# Power_3V3_Regulator.net
KiCad netlist of a schematic drawn in Altium Designer
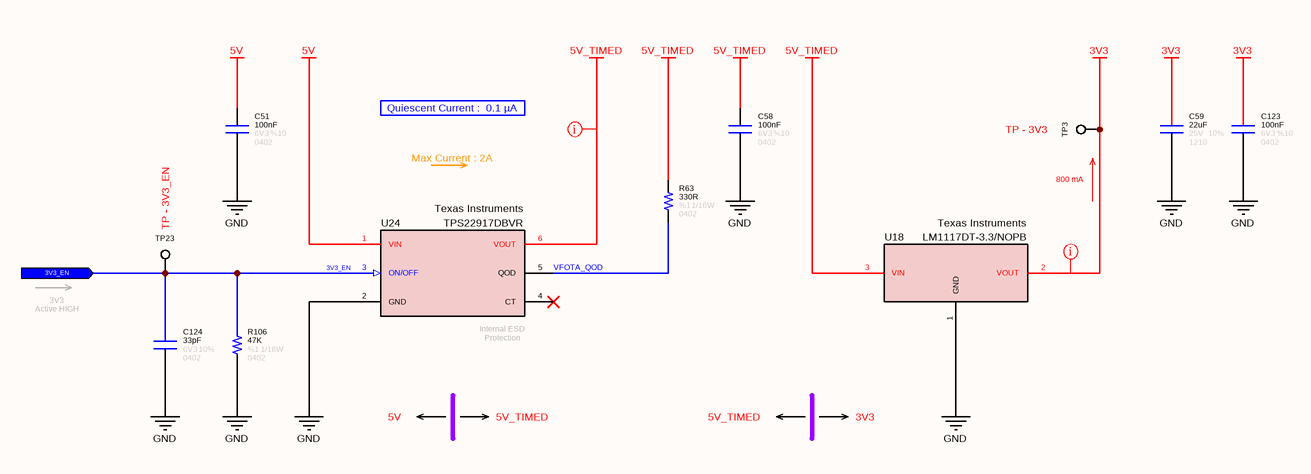
[diagram p0: Power 3V3 Regulator.SchDoc]

(export (version "E")
  (design (tool "Eeschema 10.0.6"))
  (components
    (comp (ref "C51")
      (value "100nF")
      (footprint "CAPACITOR_0402")
      (description "Capacitor - 100nF [0402-6V3] (Ceramic)")
      (fields
        (field (name "MANUFACTURER PART NUMBER") "04026D104KAT4A")
        (field (name "TOLERANCE") "%10")
        (field (name "VOLTAGE") "6V3")
        (field (name "CASE") "0402")
        (field (name "Comment") "Capacitor - 100nF [0402] (Ceramic)")
      )
      (libsource (lib "Akkoyun") (part "Capacitor - 100nF [0402-6V3]"))
    )
    (comp (ref "C58")
      (value "100nF")
      (footprint "CAPACITOR_0402")
      (description "Capacitor - 100nF [0402-6V3] (Ceramic)")
      (fields
        (field (name "MANUFACTURER PART NUMBER") "04026D104KAT4A")
        (field (name "TOLERANCE") "%10")
        (field (name "VOLTAGE") "6V3")
        (field (name "CASE") "0402")
        (field (name "Comment") "Capacitor - 100nF [0402] (Ceramic)")
      )
      (libsource (lib "Akkoyun") (part "Capacitor - 100nF [0402-6V3]"))
    )
    (comp (ref "C59")
      (value "22uF")
      (footprint "CAPACITOR_0603")
      (description "Multilayer Ceramic Capacitors MLCC - SMD/SMT 22UF 25V 10% 1210")
      (fields
        (field (name "MANUFACTURER PART NUMBER") "GRM32ER71E226KE15L")
        (field (name "TOLERANCE") "10%")
        (field (name "CASE") "1210")
        (field (name "VOLTAGE") "25V")
        (field (name "Comment") "Capacitor - 22uF [1210] (Ceramic)")
      )
      (libsource (lib "Akkoyun") (part "Capacitor - 22uF [1210-6V3]"))
    )
    (comp (ref "C123")
      (value "100nF")
      (footprint "CAPACITOR_0402")
      (description "Capacitor - 100nF [0402-6V3] (Ceramic)")
      (fields
        (field (name "MANUFACTURER PART NUMBER") "04026D104KAT4A")
        (field (name "TOLERANCE") "%10")
        (field (name "VOLTAGE") "6V3")
        (field (name "CASE") "0402")
        (field (name "Comment") "Capacitor - 100nF [0402] (Ceramic)")
      )
      (libsource (lib "Akkoyun") (part "Capacitor - 100nF [0402-6V3]"))
    )
    (comp (ref "C124")
      (value "33pF")
      (footprint "CAPACITOR_0402")
      (description "Capacitor - 33pF [0402] (Ceramic)")
      (fields
        (field (name "MANUFACTURER PART NUMBER") "C0402C330J9RACAUTO")
        (field (name "TOLERANCE") "10%")
        (field (name "CASE") "0402")
        (field (name "VOLTAGE") "6V3")
      )
      (libsource (lib "Akkoyun") (part "Capacitor - 33pF [0402-6V3]"))
    )
    (comp (ref "R63")
      (value "330R")
      (footprint "RESISTOR_0402")
      (description "Thick Film Resistors - SMD 1/16 W 330 Ohm 1%")
      (fields
        (field (name "MANUFACTURER PART NUMBER") "CRCW0402330RFKED")
        (field (name "CASE") "0402")
        (field (name "TOLERANCE") "%1")
        (field (name "POWER") "1/16W")
        (field (name "Comment") "330R - 0402 - %1 - 1/16W")
      )
      (libsource (lib "Akkoyun") (part "Resistor - 330R [0402]"))
    )
    (comp (ref "R106")
      (value "47K")
      (footprint "RESISTOR_0402")
      (description "Thick Film Resistors - SMD 1/16 W 47 KOhm 1%")
      (fields
        (field (name "MANUFACTURER PART NUMBER") "CRCW040247K0FKED")
        (field (name "TOLERANCE") "%1")
        (field (name "CASE") "0402")
        (field (name "POWER") "1/16W")
        (field (name "Comment") "47K - 0402 - %1 - 1/16W")
      )
      (libsource (lib "Akkoyun") (part "Resistor - 47K [0402]"))
    )
    (comp (ref "TP3")
      (value "TP - 3V3")
      (footprint "TP")
      (description "Test Point")
      (libsource (lib "Akkoyun") (part "PCB - Test Point"))
    )
    (comp (ref "TP23")
      (value "TP - 3V3_EN")
      (footprint "TP")
      (description "Test Point")
      (libsource (lib "Akkoyun") (part "PCB - Test Point"))
    )
    (comp (ref "U18")
      (value "LDO Regulator")
      (footprint "TO-252")
      (description "LDO Voltage Regulators 800MA LDO LINEAR REG")
      (fields
        (field (name "MANUFACTURER PART NUMBER") "LM1117DT-3.3/NOPB")
        (field (name "MANUFACTURER NAME") "Texas Instruments")
      )
      (libsource (lib "Akkoyun") (part "IC - LM1117DT-3.3/NOPB"))
    )
    (comp (ref "U24")
      (value "Power Switch")
      (footprint "SOT-23-6")
      (description "Power Switch MosFet")
      (fields
        (field (name "MANUFACTURER PART NUMBER") "TPS22917DBVR")
        (field (name "MANUFACTURER NAME") "Texas Instruments")
      )
      (libsource (lib "Akkoyun") (part "IC - TPS22917"))
    )
  )
  (nets
    (net (code "1") (name "/3V3_EN") (class "Default")
      (node (ref "C124") (pin "2") (pinfunction "2_2") (pintype "passive"))
      (node (ref "R106") (pin "2") (pinfunction "2_2") (pintype "passive"))
      (node (ref "TP23") (pin "1") (pinfunction "1_1") (pintype "passive"))
      (node (ref "U24") (pin "3") (pinfunction "ON/OFF_3") (pintype "input"))
    )
    (net (code "2") (name "/VFOTA_QOD") (class "Default")
      (node (ref "R63") (pin "1") (pinfunction "1_1") (pintype "passive"))
      (node (ref "U24") (pin "5") (pinfunction "QOD_5") (pintype "power_in"))
    )
    (net (code "3") (name "3V3") (class "Default")
      (node (ref "C123") (pin "2") (pinfunction "2_2") (pintype "passive"))
      (node (ref "C59") (pin "2") (pinfunction "2_2") (pintype "passive"))
      (node (ref "TP3") (pin "1") (pinfunction "1_1") (pintype "passive"))
      (node (ref "U18") (pin "2") (pinfunction "VOUT_2") (pintype "power_in"))
    )
    (net (code "4") (name "5V") (class "Default")
      (node (ref "C51") (pin "2") (pinfunction "2_2") (pintype "passive"))
      (node (ref "U24") (pin "1") (pinfunction "VIN_1") (pintype "power_in"))
    )
    (net (code "5") (name "5V_TIMED") (class "Default")
      (node (ref "C58") (pin "2") (pinfunction "2_2") (pintype "passive"))
      (node (ref "R63") (pin "2") (pinfunction "2_2") (pintype "passive"))
      (node (ref "U18") (pin "3") (pinfunction "VIN_3") (pintype "power_in"))
      (node (ref "U24") (pin "6") (pinfunction "VOUT_6") (pintype "power_in"))
    )
    (net (code "6") (name "GND") (class "Default")
      (node (ref "C123") (pin "1") (pinfunction "1_1") (pintype "passive"))
      (node (ref "C124") (pin "1") (pinfunction "1_1") (pintype "passive"))
      (node (ref "C51") (pin "1") (pinfunction "1_1") (pintype "passive"))
      (node (ref "C58") (pin "1") (pinfunction "1_1") (pintype "passive"))
      (node (ref "C59") (pin "1") (pinfunction "1_1") (pintype "passive"))
      (node (ref "R106") (pin "1") (pinfunction "1_1") (pintype "passive"))
      (node (ref "U18") (pin "1") (pinfunction "GND_1") (pintype "power_in"))
      (node (ref "U24") (pin "2") (pinfunction "GND_2") (pintype "power_in"))
    )
    (net (code "7") (name "unconnected-(U24-CT-Pad4)") (class "Default")
      (node (ref "U24") (pin "4") (pinfunction "CT_4") (pintype "power_in+no_connect"))
    )
  )
)
